# reference_module.net
KiCad netlist of a schematic drawn in EAGLE
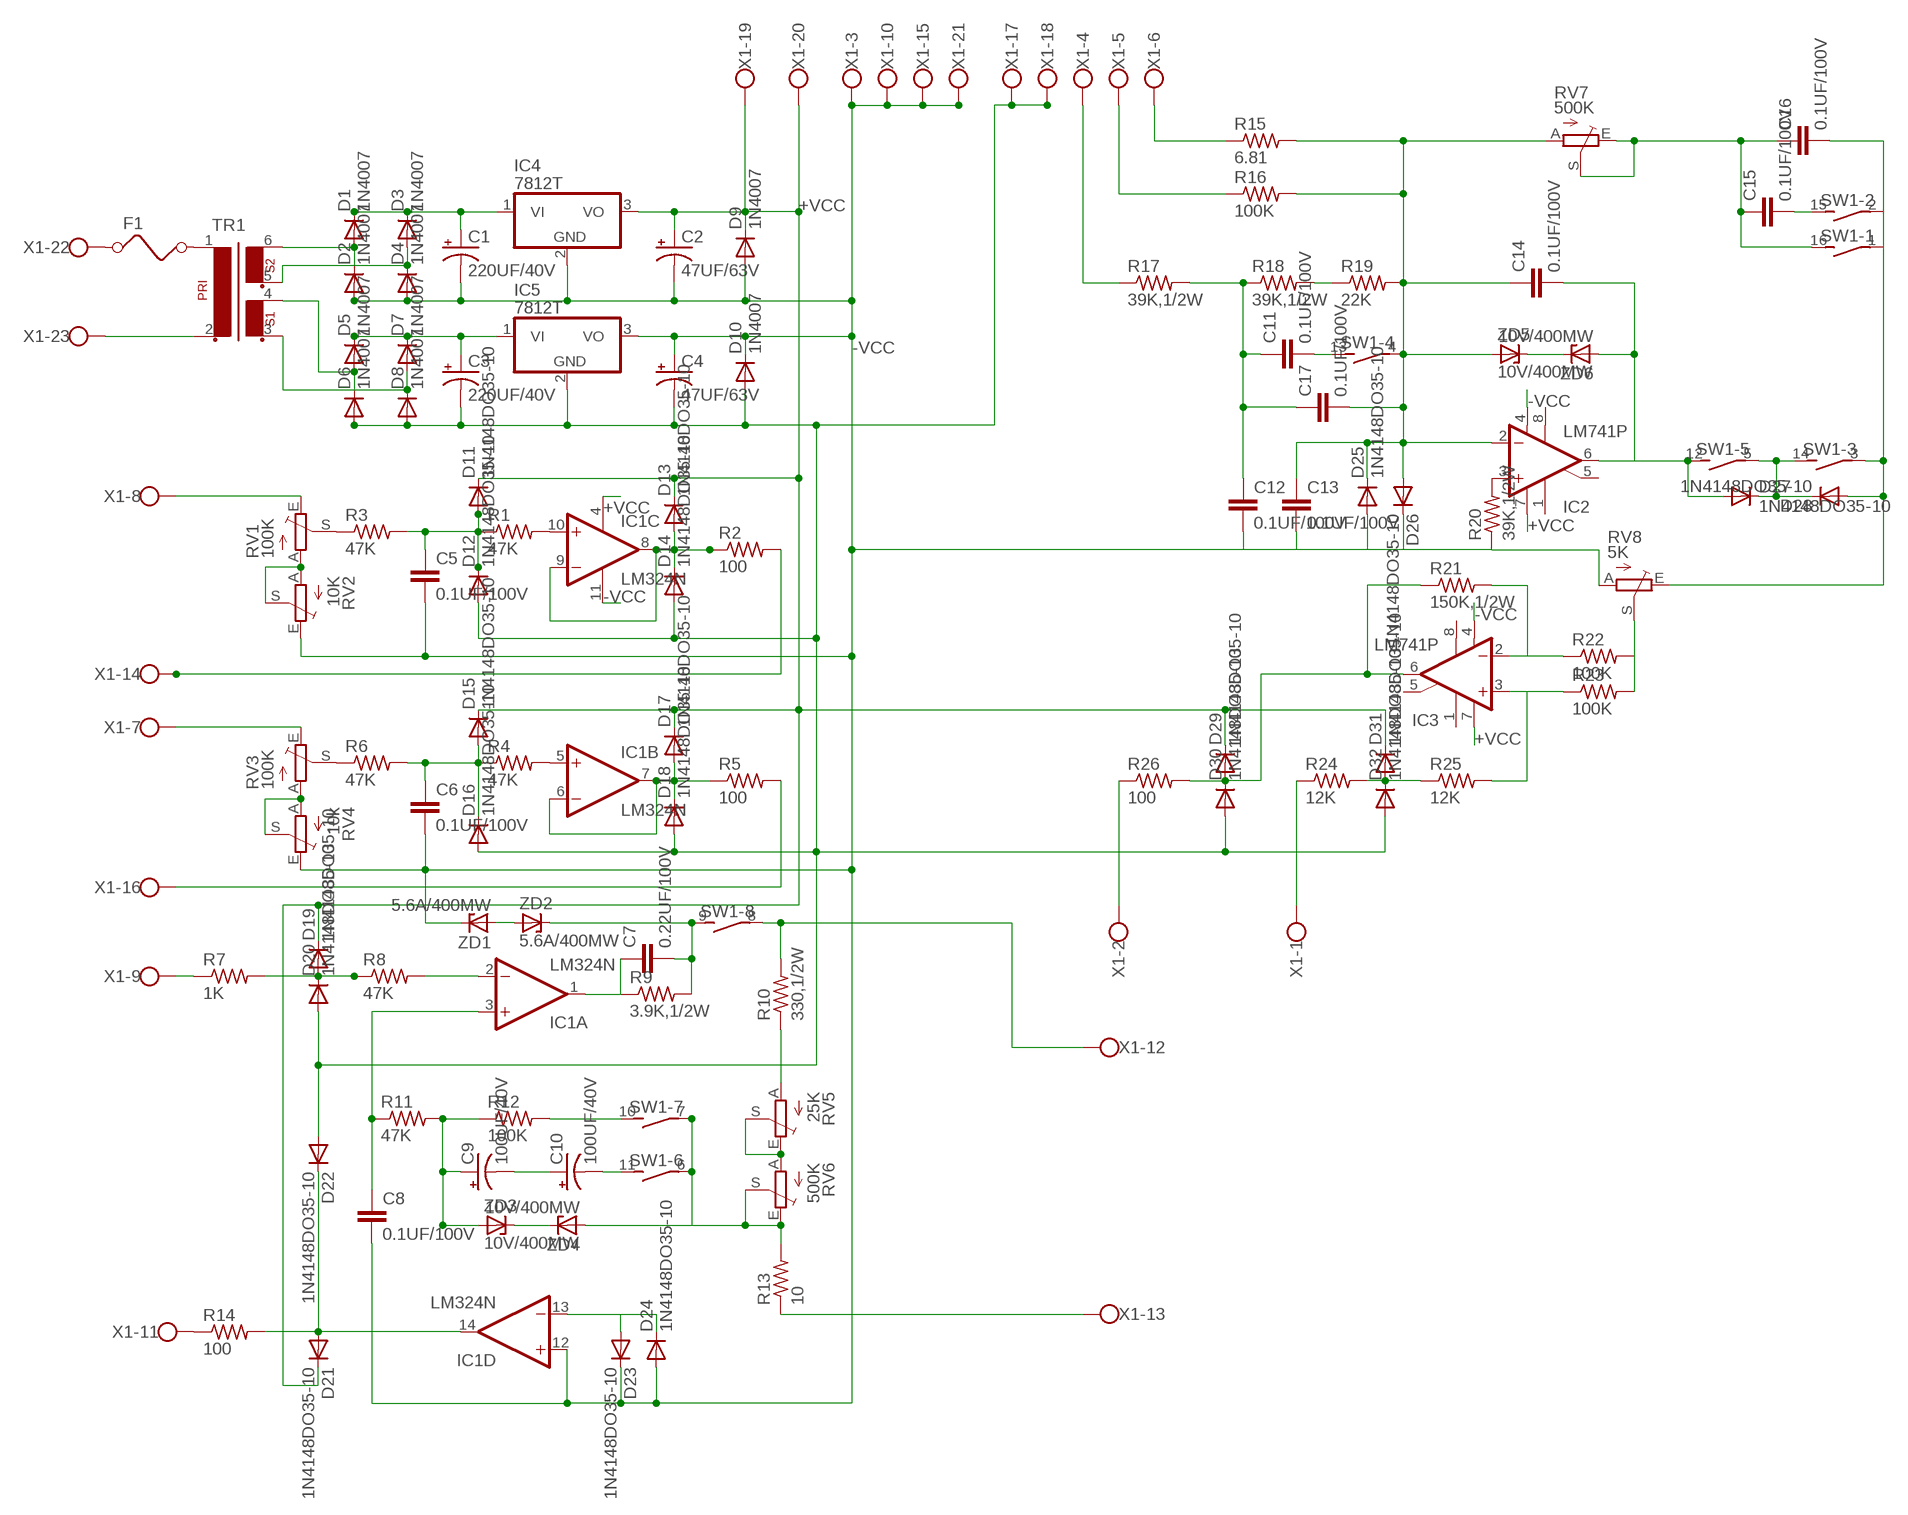
[diagram p0: schematic, sheet 1]

(export (version "E")
  (design (tool "Eeschema 10.0.6"))
  (components
    (comp (ref "C1")
      (value "220UF/40V")
      (footprint "eagle-import:E3,5-10")
      (libsource (lib "eagle-import") (part "CPOL-USE3.5-10"))
    )
    (comp (ref "C2")
      (value "47UF/63V")
      (footprint "eagle-import:E3,5-10")
      (libsource (lib "eagle-import") (part "CPOL-USE3.5-10"))
    )
    (comp (ref "C3")
      (value "220UF/40V")
      (footprint "eagle-import:E3,5-10")
      (libsource (lib "eagle-import") (part "CPOL-USE3.5-10"))
    )
    (comp (ref "C4")
      (value "47UF/63V")
      (footprint "eagle-import:E3,5-10")
      (libsource (lib "eagle-import") (part "CPOL-USE3.5-10"))
    )
    (comp (ref "C5")
      (value "0.1UF/100V")
      (footprint "eagle-import:C102-054X133")
      (libsource (lib "eagle-import") (part "C-EU102-054X133"))
    )
    (comp (ref "C6")
      (value "0.1UF/100V")
      (footprint "eagle-import:C102-054X133")
      (libsource (lib "eagle-import") (part "C-EU102-054X133"))
    )
    (comp (ref "C7")
      (value "0.22UF/100V")
      (footprint "eagle-import:C102-054X133")
      (libsource (lib "eagle-import") (part "C-EU102-054X133"))
    )
    (comp (ref "C8")
      (value "0.1UF/100V")
      (footprint "eagle-import:C102-054X133")
      (libsource (lib "eagle-import") (part "C-EU102-054X133"))
    )
    (comp (ref "C9")
      (value "100UF/40V")
      (footprint "eagle-import:E3,5-10")
      (libsource (lib "eagle-import") (part "CPOL-USE3.5-10"))
    )
    (comp (ref "C10")
      (value "100UF/40V")
      (footprint "eagle-import:E3,5-10")
      (libsource (lib "eagle-import") (part "CPOL-USE3.5-10"))
    )
    (comp (ref "C11")
      (value "0.1UF/100V")
      (footprint "eagle-import:C102-054X133")
      (libsource (lib "eagle-import") (part "C-EU102-054X133"))
    )
    (comp (ref "C12")
      (value "0.1UF/100V")
      (footprint "eagle-import:C102-054X133")
      (libsource (lib "eagle-import") (part "C-EU102-054X133"))
    )
    (comp (ref "C13")
      (value "0.1UF/100V")
      (footprint "eagle-import:C102-054X133")
      (libsource (lib "eagle-import") (part "C-EU102-054X133"))
    )
    (comp (ref "C14")
      (value "0.1UF/100V")
      (footprint "eagle-import:C102-054X133")
      (libsource (lib "eagle-import") (part "C-EU102-054X133"))
    )
    (comp (ref "C15")
      (value "0.1UF/100V")
      (footprint "eagle-import:C102-054X133")
      (libsource (lib "eagle-import") (part "C-EU102-054X133"))
    )
    (comp (ref "C16")
      (value "0.1UF/100V")
      (footprint "eagle-import:C102-054X133")
      (libsource (lib "eagle-import") (part "C-EU102-054X133"))
    )
    (comp (ref "C17")
      (value "0.1UF/100V")
      (footprint "eagle-import:C102-054X133")
      (libsource (lib "eagle-import") (part "C-EU102-054X133"))
    )
    (comp (ref "D1")
      (value "1N4007")
      (footprint "eagle-import:DO41-10")
      (libsource (lib "eagle-import") (part "1N4004"))
    )
    (comp (ref "D2")
      (value "1N4007")
      (footprint "eagle-import:DO41-10")
      (libsource (lib "eagle-import") (part "1N4004"))
    )
    (comp (ref "D3")
      (value "1N4007")
      (footprint "eagle-import:DO41-10")
      (libsource (lib "eagle-import") (part "1N4004"))
    )
    (comp (ref "D4")
      (value "1N4007")
      (footprint "eagle-import:DO41-10")
      (libsource (lib "eagle-import") (part "1N4004"))
    )
    (comp (ref "D5")
      (value "1N4007")
      (footprint "eagle-import:DO41-10")
      (libsource (lib "eagle-import") (part "1N4004"))
    )
    (comp (ref "D6")
      (value "1N4007")
      (footprint "eagle-import:DO41-10")
      (libsource (lib "eagle-import") (part "1N4004"))
    )
    (comp (ref "D7")
      (value "1N4007")
      (footprint "eagle-import:DO41-10")
      (libsource (lib "eagle-import") (part "1N4004"))
    )
    (comp (ref "D8")
      (value "1N4007")
      (footprint "eagle-import:DO41-10")
      (libsource (lib "eagle-import") (part "1N4004"))
    )
    (comp (ref "D9")
      (value "1N4007")
      (footprint "eagle-import:DO41-10")
      (libsource (lib "eagle-import") (part "1N4004"))
    )
    (comp (ref "D10")
      (value "1N4007")
      (footprint "eagle-import:DO41-10")
      (libsource (lib "eagle-import") (part "1N4004"))
    )
    (comp (ref "D11")
      (value "1N4148DO35-10")
      (footprint "eagle-import:DO35-10")
      (libsource (lib "eagle-import") (part "1N4148DO35-10"))
    )
    (comp (ref "D12")
      (value "1N4148DO35-10")
      (footprint "eagle-import:DO35-10")
      (libsource (lib "eagle-import") (part "1N4148DO35-10"))
    )
    (comp (ref "D13")
      (value "1N4148DO35-10")
      (footprint "eagle-import:DO35-10")
      (libsource (lib "eagle-import") (part "1N4148DO35-10"))
    )
    (comp (ref "D14")
      (value "1N4148DO35-10")
      (footprint "eagle-import:DO35-10")
      (libsource (lib "eagle-import") (part "1N4148DO35-10"))
    )
    (comp (ref "D15")
      (value "1N4148DO35-10")
      (footprint "eagle-import:DO35-10")
      (libsource (lib "eagle-import") (part "1N4148DO35-10"))
    )
    (comp (ref "D16")
      (value "1N4148DO35-10")
      (footprint "eagle-import:DO35-10")
      (libsource (lib "eagle-import") (part "1N4148DO35-10"))
    )
    (comp (ref "D17")
      (value "1N4148DO35-10")
      (footprint "eagle-import:DO35-10")
      (libsource (lib "eagle-import") (part "1N4148DO35-10"))
    )
    (comp (ref "D18")
      (value "1N4148DO35-10")
      (footprint "eagle-import:DO35-10")
      (libsource (lib "eagle-import") (part "1N4148DO35-10"))
    )
    (comp (ref "D19")
      (value "1N4148DO35-10")
      (footprint "eagle-import:DO35-10")
      (libsource (lib "eagle-import") (part "1N4148DO35-10"))
    )
    (comp (ref "D20")
      (value "1N4148DO35-10")
      (footprint "eagle-import:DO35-10")
      (libsource (lib "eagle-import") (part "1N4148DO35-10"))
    )
    (comp (ref "D21")
      (value "1N4148DO35-10")
      (footprint "eagle-import:DO35-10")
      (libsource (lib "eagle-import") (part "1N4148DO35-10"))
    )
    (comp (ref "D22")
      (value "1N4148DO35-10")
      (footprint "eagle-import:DO35-10")
      (libsource (lib "eagle-import") (part "1N4148DO35-10"))
    )
    (comp (ref "D23")
      (value "1N4148DO35-10")
      (footprint "eagle-import:DO35-10")
      (libsource (lib "eagle-import") (part "1N4148DO35-10"))
    )
    (comp (ref "D24")
      (value "1N4148DO35-10")
      (footprint "eagle-import:DO35-10")
      (libsource (lib "eagle-import") (part "1N4148DO35-10"))
    )
    (comp (ref "D25")
      (value "1N4148DO35-10")
      (footprint "eagle-import:DO35-10")
      (libsource (lib "eagle-import") (part "1N4148DO35-10"))
    )
    (comp (ref "D26")
      (value "1N4148DO35-10")
      (footprint "eagle-import:DO35-10")
      (libsource (lib "eagle-import") (part "1N4148DO35-10"))
    )
    (comp (ref "D27")
      (value "1N4148DO35-10")
      (footprint "eagle-import:DO35-10")
      (libsource (lib "eagle-import") (part "1N4148DO35-10"))
    )
    (comp (ref "D28")
      (value "1N4148DO35-10")
      (footprint "eagle-import:DO35-10")
      (libsource (lib "eagle-import") (part "1N4148DO35-10"))
    )
    (comp (ref "D29")
      (value "1N4148DO35-10")
      (footprint "eagle-import:DO35-10")
      (libsource (lib "eagle-import") (part "1N4148DO35-10"))
    )
    (comp (ref "D30")
      (value "1N4148DO35-10")
      (footprint "eagle-import:DO35-10")
      (libsource (lib "eagle-import") (part "1N4148DO35-10"))
    )
    (comp (ref "D31")
      (value "1N4148DO35-10")
      (footprint "eagle-import:DO35-10")
      (libsource (lib "eagle-import") (part "1N4148DO35-10"))
    )
    (comp (ref "D32")
      (value "1N4148DO35-10")
      (footprint "eagle-import:DO35-10")
      (libsource (lib "eagle-import") (part "1N4148DO35-10"))
    )
    (comp (ref "F1")
      (value "FUSE")
      (footprint "eagle-import:FUSE")
      (libsource (lib "eagle-import") (part "FUSE"))
    )
    (comp (ref "IC1")
      (value "LM324N")
      (footprint "eagle-import:DIL14")
      (libsource (lib "eagle-import") (part "LM324N"))
    )
    (comp (ref "IC2")
      (value "LM741P")
      (footprint "eagle-import:DIL08")
      (libsource (lib "eagle-import") (part "741PLM"))
    )
    (comp (ref "IC3")
      (value "LM741P")
      (footprint "eagle-import:DIL08")
      (libsource (lib "eagle-import") (part "741PLM"))
    )
    (comp (ref "IC4")
      (value "7812T")
      (footprint "eagle-import:TO220H")
      (libsource (lib "eagle-import") (part "78T12"))
    )
    (comp (ref "IC5")
      (value "7812T")
      (footprint "eagle-import:TO220H")
      (libsource (lib "eagle-import") (part "78T12"))
    )
    (comp (ref "R1")
      (value "47K")
      (footprint "eagle-import:0207_10")
      (libsource (lib "eagle-import") (part "R-US_0207/10"))
    )
    (comp (ref "R2")
      (value "100")
      (footprint "eagle-import:0207_10")
      (libsource (lib "eagle-import") (part "R-US_0207/10"))
    )
    (comp (ref "R3")
      (value "47K")
      (footprint "eagle-import:0207_10")
      (libsource (lib "eagle-import") (part "R-US_0207/10"))
    )
    (comp (ref "R4")
      (value "47K")
      (footprint "eagle-import:0207_10")
      (libsource (lib "eagle-import") (part "R-US_0207/10"))
    )
    (comp (ref "R5")
      (value "100")
      (footprint "eagle-import:0207_10")
      (libsource (lib "eagle-import") (part "R-US_0207/10"))
    )
    (comp (ref "R6")
      (value "47K")
      (footprint "eagle-import:0207_10")
      (libsource (lib "eagle-import") (part "R-US_0207/10"))
    )
    (comp (ref "R7")
      (value "1K")
      (footprint "eagle-import:0207_10")
      (libsource (lib "eagle-import") (part "R-US_0207/10"))
    )
    (comp (ref "R8")
      (value "47K")
      (footprint "eagle-import:0207_10")
      (libsource (lib "eagle-import") (part "R-US_0207/10"))
    )
    (comp (ref "R9")
      (value "3.9K,1/2W")
      (footprint "eagle-import:0207_10")
      (libsource (lib "eagle-import") (part "R-US_0207/10"))
    )
    (comp (ref "R10")
      (value "330,1/2W")
      (footprint "eagle-import:0207_10")
      (libsource (lib "eagle-import") (part "R-US_0207/10"))
    )
    (comp (ref "R11")
      (value "47K")
      (footprint "eagle-import:0207_10")
      (libsource (lib "eagle-import") (part "R-US_0207/10"))
    )
    (comp (ref "R12")
      (value "100K")
      (footprint "eagle-import:0207_10")
      (libsource (lib "eagle-import") (part "R-US_0207/10"))
    )
    (comp (ref "R13")
      (value "10")
      (footprint "eagle-import:0207_10")
      (libsource (lib "eagle-import") (part "R-US_0207/10"))
    )
    (comp (ref "R14")
      (value "100")
      (footprint "eagle-import:0207_10")
      (libsource (lib "eagle-import") (part "R-US_0207/10"))
    )
    (comp (ref "R15")
      (value "6.81")
      (footprint "eagle-import:0207_10")
      (libsource (lib "eagle-import") (part "R-US_0207/10"))
    )
    (comp (ref "R16")
      (value "100K")
      (footprint "eagle-import:0207_10")
      (libsource (lib "eagle-import") (part "R-US_0207/10"))
    )
    (comp (ref "R17")
      (value "39K,1/2W")
      (footprint "eagle-import:0207_10")
      (libsource (lib "eagle-import") (part "R-US_0207/10"))
    )
    (comp (ref "R18")
      (value "39K,1/2W")
      (footprint "eagle-import:0207_10")
      (libsource (lib "eagle-import") (part "R-US_0207/10"))
    )
    (comp (ref "R19")
      (value "22K")
      (footprint "eagle-import:0207_10")
      (libsource (lib "eagle-import") (part "R-US_0207/10"))
    )
    (comp (ref "R20")
      (value "39K,1/2W")
      (footprint "eagle-import:0207_10")
      (libsource (lib "eagle-import") (part "R-US_0207/10"))
    )
    (comp (ref "R21")
      (value "150K,1/2W")
      (footprint "eagle-import:0207_10")
      (libsource (lib "eagle-import") (part "R-US_0207/10"))
    )
    (comp (ref "R22")
      (value "100K")
      (footprint "eagle-import:0207_10")
      (libsource (lib "eagle-import") (part "R-US_0207/10"))
    )
    (comp (ref "R23")
      (value "100K")
      (footprint "eagle-import:0207_10")
      (libsource (lib "eagle-import") (part "R-US_0207/10"))
    )
    (comp (ref "R24")
      (value "12K")
      (footprint "eagle-import:0207_10")
      (libsource (lib "eagle-import") (part "R-US_0207/10"))
    )
    (comp (ref "R25")
      (value "12K")
      (footprint "eagle-import:0207_10")
      (libsource (lib "eagle-import") (part "R-US_0207/10"))
    )
    (comp (ref "R26")
      (value "100")
      (footprint "eagle-import:0207_10")
      (libsource (lib "eagle-import") (part "R-US_0207/10"))
    )
    (comp (ref "RV1")
      (value "100K")
      (footprint "eagle-import:S63P")
      (libsource (lib "eagle-import") (part "TRIM_EU-S63P"))
    )
    (comp (ref "RV2")
      (value "10K")
      (footprint "eagle-import:S63P")
      (libsource (lib "eagle-import") (part "TRIM_EU-S63P"))
    )
    (comp (ref "RV3")
      (value "100K")
      (footprint "eagle-import:S63P")
      (libsource (lib "eagle-import") (part "TRIM_EU-S63P"))
    )
    (comp (ref "RV4")
      (value "10k")
      (footprint "eagle-import:S63P")
      (libsource (lib "eagle-import") (part "TRIM_EU-S63P"))
    )
    (comp (ref "RV5")
      (value "25K")
      (footprint "eagle-import:S63P")
      (libsource (lib "eagle-import") (part "TRIM_EU-S63P"))
    )
    (comp (ref "RV6")
      (value "500K")
      (footprint "eagle-import:S63P")
      (libsource (lib "eagle-import") (part "TRIM_EU-S63P"))
    )
    (comp (ref "RV7")
      (value "500K")
      (footprint "eagle-import:S63P")
      (libsource (lib "eagle-import") (part "TRIM_EU-S63P"))
    )
    (comp (ref "RV8")
      (value "5K")
      (footprint "eagle-import:S63P")
      (libsource (lib "eagle-import") (part "TRIM_EU-S63P"))
    )
    (comp (ref "SW1")
      (value "DIP08S")
      (footprint "eagle-import:DIP08S")
      (libsource (lib "eagle-import") (part "DIP08S"))
    )
    (comp (ref "TR1")
      (value "VR2230-2")
      (footprint "eagle-import:VR22-2")
      (libsource (lib "eagle-import") (part "VR2230-2"))
    )
    (comp (ref "X1")
      (value "W237-6")
      (footprint "eagle-import:W237-6")
      (libsource (lib "eagle-import") (part "W237-6"))
    )
    (comp (ref "ZD1")
      (value "5.6A/400MW")
      (footprint "eagle-import:ZDIO-10")
      (libsource (lib "eagle-import") (part "ZENER-DIODEZD-10"))
    )
    (comp (ref "ZD2")
      (value "5.6A/400MW")
      (footprint "eagle-import:ZDIO-10")
      (libsource (lib "eagle-import") (part "ZENER-DIODEZD-10"))
    )
    (comp (ref "ZD3")
      (value "10V/400MW")
      (footprint "eagle-import:ZDIO-10")
      (libsource (lib "eagle-import") (part "ZENER-DIODEZD-10"))
    )
    (comp (ref "ZD4")
      (value "10V/400MW")
      (footprint "eagle-import:ZDIO-10")
      (libsource (lib "eagle-import") (part "ZENER-DIODEZD-10"))
    )
    (comp (ref "ZD5")
      (value "10V/400MW")
      (footprint "eagle-import:ZDIO-10")
      (libsource (lib "eagle-import") (part "ZENER-DIODEZD-10"))
    )
    (comp (ref "ZD6")
      (value "10V/400MW")
      (footprint "eagle-import:ZDIO-10")
      (libsource (lib "eagle-import") (part "ZENER-DIODEZD-10"))
    )
  )
  (nets
    (net (code "1") (name "/+VCC") (class "Default")
      (node (ref "C2") (pin "+") (pinfunction "+_+") (pintype "passive"))
      (node (ref "D11") (pin "C") (pinfunction "C_C") (pintype "passive"))
      (node (ref "D13") (pin "C") (pinfunction "C_C") (pintype "passive"))
      (node (ref "D15") (pin "C") (pinfunction "C_C") (pintype "passive"))
      (node (ref "D17") (pin "C") (pinfunction "C_C") (pintype "passive"))
      (node (ref "D19") (pin "C") (pinfunction "C_C") (pintype "passive"))
      (node (ref "D21") (pin "C") (pinfunction "C_C") (pintype "passive"))
      (node (ref "D29") (pin "C") (pinfunction "C_C") (pintype "passive"))
      (node (ref "D31") (pin "C") (pinfunction "C_C") (pintype "passive"))
      (node (ref "D9") (pin "C") (pinfunction "C_C") (pintype "passive"))
      (node (ref "IC1") (pin "4") (pinfunction "V+_4") (pintype "power_in"))
      (node (ref "IC2") (pin "7") (pinfunction "V+_7") (pintype "power_in"))
      (node (ref "IC3") (pin "7") (pinfunction "V+_7") (pintype "power_in"))
      (node (ref "IC4") (pin "3") (pinfunction "VO_3") (pintype "passive"))
      (node (ref "X1") (pin "19") (pinfunction "KL_19") (pintype "passive"))
      (node (ref "X1") (pin "20") (pinfunction "KL_20") (pintype "passive"))
    )
    (net (code "2") (name "/-VCC") (class "Default")
      (node (ref "C1") (pin "-") (pinfunction "-_-") (pintype "passive"))
      (node (ref "C12") (pin "2") (pinfunction "2_2") (pintype "passive"))
      (node (ref "C13") (pin "2") (pinfunction "2_2") (pintype "passive"))
      (node (ref "C2") (pin "-") (pinfunction "-_-") (pintype "passive"))
      (node (ref "C4") (pin "+") (pinfunction "+_+") (pintype "passive"))
      (node (ref "C5") (pin "2") (pinfunction "2_2") (pintype "passive"))
      (node (ref "C6") (pin "2") (pinfunction "2_2") (pintype "passive"))
      (node (ref "C8") (pin "2") (pinfunction "2_2") (pintype "passive"))
      (node (ref "D10") (pin "C") (pinfunction "C_C") (pintype "passive"))
      (node (ref "D2") (pin "A") (pinfunction "A_A") (pintype "passive"))
      (node (ref "D23") (pin "C") (pinfunction "C_C") (pintype "passive"))
      (node (ref "D24") (pin "A") (pinfunction "A_A") (pintype "passive"))
      (node (ref "D25") (pin "A") (pinfunction "A_A") (pintype "passive"))
      (node (ref "D26") (pin "C") (pinfunction "C_C") (pintype "passive"))
      (node (ref "D4") (pin "A") (pinfunction "A_A") (pintype "passive"))
      (node (ref "D9") (pin "A") (pinfunction "A_A") (pintype "passive"))
      (node (ref "IC1") (pin "11") (pinfunction "V-_11") (pintype "power_in"))
      (node (ref "IC1") (pin "12") (pinfunction "+IN_12") (pintype "input"))
      (node (ref "IC2") (pin "4") (pinfunction "V-_4") (pintype "power_in"))
      (node (ref "IC3") (pin "4") (pinfunction "V-_4") (pintype "power_in"))
      (node (ref "IC4") (pin "2") (pinfunction "GND_2") (pintype "passive"))
      (node (ref "IC5") (pin "3") (pinfunction "VO_3") (pintype "passive"))
      (node (ref "R20") (pin "1") (pinfunction "1_1") (pintype "passive"))
      (node (ref "RV2") (pin "E") (pinfunction "E_E") (pintype "passive"))
      (node (ref "RV4") (pin "E") (pinfunction "E_E") (pintype "passive"))
      (node (ref "RV8") (pin "A") (pinfunction "A_A") (pintype "passive"))
      (node (ref "X1") (pin "10") (pinfunction "KL_10") (pintype "passive"))
      (node (ref "X1") (pin "15") (pinfunction "KL_15") (pintype "passive"))
      (node (ref "X1") (pin "21") (pinfunction "KL_21") (pintype "passive"))
      (node (ref "X1") (pin "3") (pinfunction "KL_3") (pintype "passive"))
      (node (ref "ZD1") (pin "C") (pinfunction "C_C") (pintype "passive"))
    )
    (net (code "3") (name "Net-(C5-Pad1)") (class "Default")
      (node (ref "C5") (pin "1") (pinfunction "1_1") (pintype "passive"))
      (node (ref "D11") (pin "A") (pinfunction "A_A") (pintype "passive"))
      (node (ref "D12") (pin "C") (pinfunction "C_C") (pintype "passive"))
      (node (ref "R1") (pin "1") (pinfunction "1_1") (pintype "passive"))
      (node (ref "R3") (pin "2") (pinfunction "2_2") (pintype "passive"))
    )
    (net (code "4") (name "Net-(C6-Pad1)") (class "Default")
      (node (ref "C6") (pin "1") (pinfunction "1_1") (pintype "passive"))
      (node (ref "D15") (pin "A") (pinfunction "A_A") (pintype "passive"))
      (node (ref "D16") (pin "C") (pinfunction "C_C") (pintype "passive"))
      (node (ref "R4") (pin "1") (pinfunction "1_1") (pintype "passive"))
      (node (ref "R6") (pin "2") (pinfunction "2_2") (pintype "passive"))
    )
    (net (code "5") (name "Net-(C9-Pad+)") (class "Default")
      (node (ref "C9") (pin "+") (pinfunction "+_+") (pintype "passive"))
      (node (ref "R11") (pin "2") (pinfunction "2_2") (pintype "passive"))
      (node (ref "R12") (pin "1") (pinfunction "1_1") (pintype "passive"))
      (node (ref "ZD3") (pin "A") (pinfunction "A_A") (pintype "passive"))
    )
    (net (code "6") (name "Net-(C10-Pad+)") (class "Default")
      (node (ref "C10") (pin "+") (pinfunction "+_+") (pintype "passive"))
      (node (ref "C9") (pin "-") (pinfunction "-_-") (pintype "passive"))
    )
    (net (code "7") (name "Net-(C11-Pad1)") (class "Default")
      (node (ref "C11") (pin "1") (pinfunction "1_1") (pintype "passive"))
      (node (ref "C12") (pin "1") (pinfunction "1_1") (pintype "passive"))
      (node (ref "C17") (pin "1") (pinfunction "1_1") (pintype "passive"))
      (node (ref "R17") (pin "2") (pinfunction "2_2") (pintype "passive"))
      (node (ref "R18") (pin "1") (pinfunction "1_1") (pintype "passive"))
    )
    (net (code "8") (name "Net-(D1-PadA)") (class "Default")
      (node (ref "D1") (pin "A") (pinfunction "A_A") (pintype "passive"))
      (node (ref "D2") (pin "C") (pinfunction "C_C") (pintype "passive"))
      (node (ref "TR1") (pin "6") (pinfunction "6_6") (pintype "passive"))
    )
    (net (code "9") (name "Net-(D3-PadA)") (class "Default")
      (node (ref "D3") (pin "A") (pinfunction "A_A") (pintype "passive"))
      (node (ref "D4") (pin "C") (pinfunction "C_C") (pintype "passive"))
      (node (ref "TR1") (pin "5") (pinfunction "5_5") (pintype "passive"))
    )
    (net (code "10") (name "Net-(D5-PadA)") (class "Default")
      (node (ref "D5") (pin "A") (pinfunction "A_A") (pintype "passive"))
      (node (ref "D6") (pin "C") (pinfunction "C_C") (pintype "passive"))
      (node (ref "TR1") (pin "4") (pinfunction "4_4") (pintype "passive"))
    )
    (net (code "11") (name "Net-(D7-PadA)") (class "Default")
      (node (ref "D7") (pin "A") (pinfunction "A_A") (pintype "passive"))
      (node (ref "D8") (pin "C") (pinfunction "C_C") (pintype "passive"))
      (node (ref "TR1") (pin "3") (pinfunction "3_3") (pintype "passive"))
    )
    (net (code "12") (name "Net-(D19-PadA)") (class "Default")
      (node (ref "D19") (pin "A") (pinfunction "A_A") (pintype "passive"))
      (node (ref "D20") (pin "C") (pinfunction "C_C") (pintype "passive"))
      (node (ref "R7") (pin "2") (pinfunction "2_2") (pintype "passive"))
      (node (ref "R8") (pin "1") (pinfunction "1_1") (pintype "passive"))
    )
    (net (code "13") (name "Net-(D31-PadA)") (class "Default")
      (node (ref "D31") (pin "A") (pinfunction "A_A") (pintype "passive"))
      (node (ref "D32") (pin "C") (pinfunction "C_C") (pintype "passive"))
      (node (ref "R24") (pin "2") (pinfunction "2_2") (pintype "passive"))
      (node (ref "R25") (pin "1") (pinfunction "1_1") (pintype "passive"))
    )
    (net (code "14") (name "Net-(F1-Pad2)") (class "Default")
      (node (ref "F1") (pin "2") (pinfunction "2_2") (pintype "passive"))
      (node (ref "TR1") (pin "1") (pinfunction "1_1") (pintype "passive"))
    )
    (net (code "15") (name "Net-(IC1A-+IN)") (class "Default")
      (node (ref "C8") (pin "1") (pinfunction "1_1") (pintype "passive"))
      (node (ref "IC1") (pin "3") (pinfunction "+IN_3") (pintype "input"))
      (node (ref "R11") (pin "1") (pinfunction "1_1") (pintype "passive"))
    )
    (net (code "16") (name "Net-(IC1A--IN)") (class "Default")
      (node (ref "IC1") (pin "2") (pinfunction "-IN_2") (pintype "input"))
      (node (ref "R8") (pin "2") (pinfunction "2_2") (pintype "passive"))
    )
    (net (code "17") (name "Net-(IC1A-OUT)") (class "Default")
      (node (ref "C7") (pin "1") (pinfunction "1_1") (pintype "passive"))
      (node (ref "IC1") (pin "1") (pinfunction "OUT_1") (pintype "output"))
      (node (ref "R9") (pin "1") (pinfunction "1_1") (pintype "passive"))
    )
    (net (code "18") (name "Net-(IC1B-+IN)") (class "Default")
      (node (ref "IC1") (pin "5") (pinfunction "+IN_5") (pintype "input"))
      (node (ref "R4") (pin "2") (pinfunction "2_2") (pintype "passive"))
    )
    (net (code "19") (name "Net-(IC1B--IN)") (class "Default")
      (node (ref "D17") (pin "A") (pinfunction "A_A") (pintype "passive"))
      (node (ref "D18") (pin "C") (pinfunction "C_C") (pintype "passive"))
      (node (ref "IC1") (pin "6") (pinfunction "-IN_6") (pintype "input"))
      (node (ref "IC1") (pin "7") (pinfunction "OUT_7") (pintype "output"))
      (node (ref "R5") (pin "1") (pinfunction "1_1") (pintype "passive"))
    )
    (net (code "20") (name "Net-(IC1C-+IN)") (class "Default")
      (node (ref "IC1") (pin "10") (pinfunction "+IN_10") (pintype "input"))
      (node (ref "R1") (pin "2") (pinfunction "2_2") (pintype "passive"))
    )
    (net (code "21") (name "Net-(IC1C--IN)") (class "Default")
      (node (ref "D13") (pin "A") (pinfunction "A_A") (pintype "passive"))
      (node (ref "D14") (pin "C") (pinfunction "C_C") (pintype "passive"))
      (node (ref "IC1") (pin "8") (pinfunction "OUT_8") (pintype "output"))
      (node (ref "IC1") (pin "9") (pinfunction "-IN_9") (pintype "input"))
      (node (ref "R2") (pin "1") (pinfunction "1_1") (pintype "passive"))
    )
    (net (code "22") (name "Net-(IC1D--IN)") (class "Default")
      (node (ref "D23") (pin "A") (pinfunction "A_A") (pintype "passive"))
      (node (ref "D24") (pin "C") (pinfunction "C_C") (pintype "passive"))
      (node (ref "IC1") (pin "13") (pinfunction "-IN_13") (pintype "input"))
    )
    (net (code "23") (name "Net-(IC1D-OUT)") (class "Default")
      (node (ref "D21") (pin "A") (pinfunction "A_A") (pintype "passive"))
      (node (ref "D22") (pin "C") (pinfunction "C_C") (pintype "passive"))
      (node (ref "IC1") (pin "14") (pinfunction "OUT_14") (pintype "output"))
      (node (ref "R14") (pin "2") (pinfunction "2_2") (pintype "passive"))
    )
    (net (code "24") (name "Net-(IC2-+IN)") (class "Default")
      (node (ref "IC2") (pin "3") (pinfunction "+IN_3") (pintype "input"))
      (node (ref "R20") (pin "2") (pinfunction "2_2") (pintype "passive"))
    )
    (net (code "25") (name "Net-(IC2--IN)") (class "Default")
      (node (ref "C13") (pin "1") (pinfunction "1_1") (pintype "passive"))
      (node (ref "C14") (pin "1") (pinfunction "1_1") (pintype "passive"))
      (node (ref "C17") (pin "2") (pinfunction "2_2") (pintype "passive"))
      (node (ref "D25") (pin "C") (pinfunction "C_C") (pintype "passive"))
      (node (ref "D26") (pin "A") (pinfunction "A_A") (pintype "passive"))
      (node (ref "IC2") (pin "2") (pinfunction "-IN_2") (pintype "input"))
      (node (ref "R15") (pin "2") (pinfunction "2_2") (pintype "passive"))
      (node (ref "R16") (pin "2") (pinfunction "2_2") (pintype "passive"))
      (node (ref "R19") (pin "2") (pinfunction "2_2") (pintype "passive"))
      (node (ref "RV7") (pin "A") (pinfunction "A_A") (pintype "passive"))
      (node (ref "SW1") (pin "4") (pinfunction "1_4") (pintype "passive"))
      (node (ref "ZD5") (pin "A") (pinfunction "A_A") (pintype "passive"))
    )
    (net (code "26") (name "Net-(IC2-OUT)") (class "Default")
      (node (ref "C14") (pin "2") (pinfunction "2_2") (pintype "passive"))
      (node (ref "D27") (pin "A") (pinfunction "A_A") (pintype "passive"))
      (node (ref "IC2") (pin "6") (pinfunction "OUT_6") (pintype "output"))
      (node (ref "SW1") (pin "12") (pinfunction "2_12") (pintype "passive"))
      (node (ref "ZD6") (pin "A") (pinfunction "A_A") (pintype "passive"))
    )
    (net (code "27") (name "Net-(IC3-+IN)") (class "Default")
      (node (ref "IC3") (pin "3") (pinfunction "+IN_3") (pintype "input"))
      (node (ref "R23") (pin "1") (pinfunction "1_1") (pintype "passive"))
      (node (ref "R25") (pin "2") (pinfunction "2_2") (pintype "passive"))
    )
    (net (code "28") (name "Net-(IC3--IN)") (class "Default")
      (node (ref "IC3") (pin "2") (pinfunction "-IN_2") (pintype "input"))
      (node (ref "R21") (pin "2") (pinfunction "2_2") (pintype "passive"))
      (node (ref "R22") (pin "1") (pinfunction "1_1") (pintype "passive"))
    )
    (net (code "29") (name "Net-(IC3-OUT)") (class "Default")
      (node (ref "D29") (pin "A") (pinfunction "A_A") (pintype "passive"))
      (node (ref "D30") (pin "C") (pinfunction "C_C") (pintype "passive"))
      (node (ref "IC3") (pin "6") (pinfunction "OUT_6") (pintype "output"))
      (node (ref "R21") (pin "1") (pinfunction "1_1") (pintype "passive"))
      (node (ref "R26") (pin "2") (pinfunction "2_2") (pintype "passive"))
    )
    (net (code "30") (name "Net-(IC4-VI)") (class "Default")
      (node (ref "C1") (pin "+") (pinfunction "+_+") (pintype "passive"))
      (node (ref "D1") (pin "C") (pinfunction "C_C") (pintype "passive"))
      (node (ref "D3") (pin "C") (pinfunction "C_C") (pintype "passive"))
      (node (ref "IC4") (pin "1") (pinfunction "VI_1") (pintype "input"))
    )
    (net (code "31") (name "Net-(IC5-GND)") (class "Default")
      (node (ref "C3") (pin "-") (pinfunction "-_-") (pintype "passive"))
      (node (ref "C4") (pin "-") (pinfunction "-_-") (pintype "passive"))
      (node (ref "D10") (pin "A") (pinfunction "A_A") (pintype "passive"))
      (node (ref "D12") (pin "A") (pinfunction "A_A") (pintype "passive"))
      (node (ref "D14") (pin "A") (pinfunction "A_A") (pintype "passive"))
      (node (ref "D16") (pin "A") (pinfunction "A_A") (pintype "passive"))
      (node (ref "D18") (pin "A") (pinfunction "A_A") (pintype "passive"))
      (node (ref "D20") (pin "A") (pinfunction "A_A") (pintype "passive"))
      (node (ref "D22") (pin "A") (pinfunction "A_A") (pintype "passive"))
      (node (ref "D30") (pin "A") (pinfunction "A_A") (pintype "passive"))
      (node (ref "D32") (pin "A") (pinfunction "A_A") (pintype "passive"))
      (node (ref "D6") (pin "A") (pinfunction "A_A") (pintype "passive"))
      (node (ref "D8") (pin "A") (pinfunction "A_A") (pintype "passive"))
      (node (ref "IC5") (pin "2") (pinfunction "GND_2") (pintype "passive"))
      (node (ref "X1") (pin "17") (pinfunction "KL_17") (pintype "passive"))
      (node (ref "X1") (pin "18") (pinfunction "KL_18") (pintype "passive"))
    )
    (net (code "32") (name "Net-(IC5-VI)") (class "Default")
      (node (ref "C3") (pin "+") (pinfunction "+_+") (pintype "passive"))
      (node (ref "D5") (pin "C") (pinfunction "C_C") (pintype "passive"))
      (node (ref "D7") (pin "C") (pinfunction "C_C") (pintype "passive"))
      (node (ref "IC5") (pin "1") (pinfunction "VI_1") (pintype "input"))
    )
    (net (code "33") (name "Net-(R3-Pad1)") (class "Default")
      (node (ref "R3") (pin "1") (pinfunction "1_1") (pintype "passive"))
      (node (ref "RV1") (pin "S") (pinfunction "S_S") (pintype "passive"))
    )
    (net (code "34") (name "Net-(R6-Pad1)") (class "Default")
      (node (ref "R6") (pin "1") (pinfunction "1_1") (pintype "passive"))
      (node (ref "RV3") (pin "S") (pinfunction "S_S") (pintype "passive"))
    )
    (net (code "35") (name "Net-(R10-Pad1)") (class "Default")
      (node (ref "R10") (pin "1") (pinfunction "1_1") (pintype "passive"))
      (node (ref "RV5") (pin "A") (pinfunction "A_A") (pintype "passive"))
    )
    (net (code "36") (name "Net-(R18-Pad2)") (class "Default")
      (node (ref "R18") (pin "2") (pinfunction "2_2") (pintype "passive"))
      (node (ref "R19") (pin "1") (pinfunction "1_1") (pintype "passive"))
    )
    (net (code "37") (name "Net-(R22-Pad2)") (class "Default")
      (node (ref "R22") (pin "2") (pinfunction "2_2") (pintype "passive"))
      (node (ref "R23") (pin "2") (pinfunction "2_2") (pintype "passive"))
      (node (ref "RV8") (pin "S") (pinfunction "S_S") (pintype "passive"))
    )
    (net (code "38") (name "Net-(RV1-PadA)") (class "Default")
      (node (ref "RV1") (pin "A") (pinfunction "A_A") (pintype "passive"))
      (node (ref "RV2") (pin "A") (pinfunction "A_A") (pintype "passive"))
      (node (ref "RV2") (pin "S") (pinfunction "S_S") (pintype "passive"))
    )
    (net (code "39") (name "Net-(RV3-PadA)") (class "Default")
      (node (ref "RV3") (pin "A") (pinfunction "A_A") (pintype "passive"))
      (node (ref "RV4") (pin "A") (pinfunction "A_A") (pintype "passive"))
      (node (ref "RV4") (pin "S") (pinfunction "S_S") (pintype "passive"))
    )
    (net (code "40") (name "Net-(RV5-PadE)") (class "Default")
      (node (ref "RV5") (pin "E") (pinfunction "E_E") (pintype "passive"))
      (node (ref "RV5") (pin "S") (pinfunction "S_S") (pintype "passive"))
      (node (ref "RV6") (pin "A") (pinfunction "A_A") (pintype "passive"))
    )
    (net (code "41") (name "Net-(SW1A-2)") (class "Default")
      (node (ref "C15") (pin "1") (pinfunction "1_1") (pintype "passive"))
      (node (ref "C16") (pin "1") (pinfunction "1_1") (pintype "passive"))
      (node (ref "RV7") (pin "E") (pinfunction "E_E") (pintype "passive"))
      (node (ref "RV7") (pin "S") (pinfunction "S_S") (pintype "passive"))
      (node (ref "SW1") (pin "16") (pinfunction "2_16") (pintype "passive"))
    )
    (net (code "42") (name "Net-(SW1B-1)") (class "Default")
      (node (ref "C16") (pin "2") (pinfunction "2_2") (pintype "passive"))
      (node (ref "D28") (pin "A") (pinfunction "A_A") (pintype "passive"))
      (node (ref "RV8") (pin "E") (pinfunction "E_E") (pintype "passive"))
      (node (ref "SW1") (pin "1") (pinfunction "1_1") (pintype "passive"))
      (node (ref "SW1") (pin "2") (pinfunction "1_2") (pintype "passive"))
      (node (ref "SW1") (pin "3") (pinfunction "1_3") (pintype "passive"))
    )
    (net (code "43") (name "Net-(SW1B-2)") (class "Default")
      (node (ref "C15") (pin "2") (pinfunction "2_2") (pintype "passive"))
      (node (ref "SW1") (pin "15") (pinfunction "2_15") (pintype "passive"))
    )
    (net (code "44") (name "Net-(SW1C-2)") (class "Default")
      (node (ref "D27") (pin "C") (pinfunction "C_C") (pintype "passive"))
      (node (ref "D28") (pin "C") (pinfunction "C_C") (pintype "passive"))
      (node (ref "SW1") (pin "14") (pinfunction "2_14") (pintype "passive"))
      (node (ref "SW1") (pin "5") (pinfunction "1_5") (pintype "passive"))
    )
    (net (code "45") (name "Net-(SW1D-2)") (class "Default")
      (node (ref "C11") (pin "2") (pinfunction "2_2") (pintype "passive"))
      (node (ref "SW1") (pin "13") (pinfunction "2_13") (pintype "passive"))
    )
    (net (code "46") (name "Net-(SW1F-1)") (class "Default")
      (node (ref "R13") (pin "2") (pinfunction "2_2") (pintype "passive"))
      (node (ref "RV6") (pin "E") (pinfunction "E_E") (pintype "passive"))
      (node (ref "RV6") (pin "S") (pinfunction "S_S") (pintype "passive"))
      (node (ref "SW1") (pin "6") (pinfunction "1_6") (pintype "passive"))
      (node (ref "SW1") (pin "7") (pinfunction "1_7") (pintype "passive"))
      (node (ref "ZD4") (pin "A") (pinfunction "A_A") (pintype "passive"))
    )
    (net (code "47") (name "Net-(SW1F-2)") (class "Default")
      (node (ref "C10") (pin "-") (pinfunction "-_-") (pintype "passive"))
      (node (ref "SW1") (pin "11") (pinfunction "2_11") (pintype "passive"))
    )
    (net (code "48") (name "Net-(SW1G-2)") (class "Default")
      (node (ref "R12") (pin "2") (pinfunction "2_2") (pintype "passive"))
      (node (ref "SW1") (pin "10") (pinfunction "2_10") (pintype "passive"))
    )
    (net (code "49") (name "Net-(SW1H-1)") (class "Default")
      (node (ref "R10") (pin "2") (pinfunction "2_2") (pintype "passive"))
      (node (ref "SW1") (pin "8") (pinfunction "1_8") (pintype "passive"))
      (node (ref "X1") (pin "12") (pinfunction "KL_12") (pintype "passive"))
    )
    (net (code "50") (name "Net-(SW1H-2)") (class "Default")
      (node (ref "C7") (pin "2") (pinfunction "2_2") (pintype "passive"))
      (node (ref "R9") (pin "2") (pinfunction "2_2") (pintype "passive"))
      (node (ref "SW1") (pin "9") (pinfunction "2_9") (pintype "passive"))
      (node (ref "ZD2") (pin "C") (pinfunction "C_C") (pintype "passive"))
    )
    (net (code "51") (name "Net-(X1A-KL)") (class "Default")
      (node (ref "R24") (pin "1") (pinfunction "1_1") (pintype "passive"))
      (node (ref "X1") (pin "1") (pinfunction "KL_1") (pintype "passive"))
    )
    (net (code "52") (name "Net-(X1C-KL)") (class "Default")
      (node (ref "R14") (pin "1") (pinfunction "1_1") (pintype "passive"))
      (node (ref "X1") (pin "11") (pinfunction "KL_11") (pintype "passive"))
    )
    (net (code "53") (name "Net-(X1E-KL)") (class "Default")
      (node (ref "R13") (pin "1") (pinfunction "1_1") (pintype "passive"))
      (node (ref "X1") (pin "13") (pinfunction "KL_13") (pintype "passive"))
    )
    (net (code "54") (name "Net-(X1F-KL)") (class "Default")
      (node (ref "R2") (pin "2") (pinfunction "2_2") (pintype "passive"))
      (node (ref "X1") (pin "14") (pinfunction "KL_14") (pintype "passive"))
    )
    (net (code "55") (name "Net-(X1H-KL)") (class "Default")
      (node (ref "R5") (pin "2") (pinfunction "2_2") (pintype "passive"))
      (node (ref "X1") (pin "16") (pinfunction "KL_16") (pintype "passive"))
    )
    (net (code "56") (name "Net-(X1L-KL)") (class "Default")
      (node (ref "R26") (pin "1") (pinfunction "1_1") (pintype "passive"))
      (node (ref "X1") (pin "2") (pinfunction "KL_2") (pintype "passive"))
    )
    (net (code "57") (name "Net-(X1O-KL)") (class "Default")
      (node (ref "F1") (pin "1") (pinfunction "1_1") (pintype "passive"))
      (node (ref "X1") (pin "22") (pinfunction "KL_22") (pintype "passive"))
    )
    (net (code "58") (name "Net-(X1P-KL)") (class "Default")
      (node (ref "TR1") (pin "2") (pinfunction "2_2") (pintype "passive"))
      (node (ref "X1") (pin "23") (pinfunction "KL_23") (pintype "passive"))
    )
    (net (code "59") (name "Net-(X1R-KL)") (class "Default")
      (node (ref "R17") (pin "1") (pinfunction "1_1") (pintype "passive"))
      (node (ref "X1") (pin "4") (pinfunction "KL_4") (pintype "passive"))
    )
    (net (code "60") (name "Net-(X1S-KL)") (class "Default")
      (node (ref "R16") (pin "1") (pinfunction "1_1") (pintype "passive"))
      (node (ref "X1") (pin "5") (pinfunction "KL_5") (pintype "passive"))
    )
    (net (code "61") (name "Net-(X1T-KL)") (class "Default")
      (node (ref "R15") (pin "1") (pinfunction "1_1") (pintype "passive"))
      (node (ref "X1") (pin "6") (pinfunction "KL_6") (pintype "passive"))
    )
    (net (code "62") (name "Net-(X1U-KL)") (class "Default")
      (node (ref "RV3") (pin "E") (pinfunction "E_E") (pintype "passive"))
      (node (ref "X1") (pin "7") (pinfunction "KL_7") (pintype "passive"))
    )
    (net (code "63") (name "Net-(X1V-KL)") (class "Default")
      (node (ref "RV1") (pin "E") (pinfunction "E_E") (pintype "passive"))
      (node (ref "X1") (pin "8") (pinfunction "KL_8") (pintype "passive"))
    )
    (net (code "64") (name "Net-(X1W-KL)") (class "Default")
      (node (ref "R7") (pin "1") (pinfunction "1_1") (pintype "passive"))
      (node (ref "X1") (pin "9") (pinfunction "KL_9") (pintype "passive"))
    )
    (net (code "65") (name "Net-(ZD1-PadA)") (class "Default")
      (node (ref "ZD1") (pin "A") (pinfunction "A_A") (pintype "passive"))
      (node (ref "ZD2") (pin "A") (pinfunction "A_A") (pintype "passive"))
    )
    (net (code "66") (name "Net-(ZD3-PadC)") (class "Default")
      (node (ref "ZD3") (pin "C") (pinfunction "C_C") (pintype "passive"))
      (node (ref "ZD4") (pin "C") (pinfunction "C_C") (pintype "passive"))
    )
    (net (code "67") (name "Net-(ZD5-PadC)") (class "Default")
      (node (ref "ZD5") (pin "C") (pinfunction "C_C") (pintype "passive"))
      (node (ref "ZD6") (pin "C") (pinfunction "C_C") (pintype "passive"))
    )
    (net (code "68") (name "unconnected-(IC2-ON1-Pad1)") (class "Default")
      (node (ref "IC2") (pin "1") (pinfunction "ON1_1") (pintype "passive"))
    )
    (net (code "69") (name "unconnected-(IC2-ON2-Pad5)") (class "Default")
      (node (ref "IC2") (pin "5") (pinfunction "ON2_5") (pintype "passive"))
    )
    (net (code "70") (name "unconnected-(IC2-OPT-Pad8)") (class "Default")
      (node (ref "IC2") (pin "8") (pinfunction "OPT_8") (pintype "passive"))
    )
    (net (code "71") (name "unconnected-(IC3-ON1-Pad1)") (class "Default")
      (node (ref "IC3") (pin "1") (pinfunction "ON1_1") (pintype "passive"))
    )
    (net (code "72") (name "unconnected-(IC3-ON2-Pad5)") (class "Default")
      (node (ref "IC3") (pin "5") (pinfunction "ON2_5") (pintype "passive"))
    )
    (net (code "73") (name "unconnected-(IC3-OPT-Pad8)") (class "Default")
      (node (ref "IC3") (pin "8") (pinfunction "OPT_8") (pintype "passive"))
    )
  )
)
